# Power_Supply.net
KiCad netlist of a schematic drawn in Altium Designer
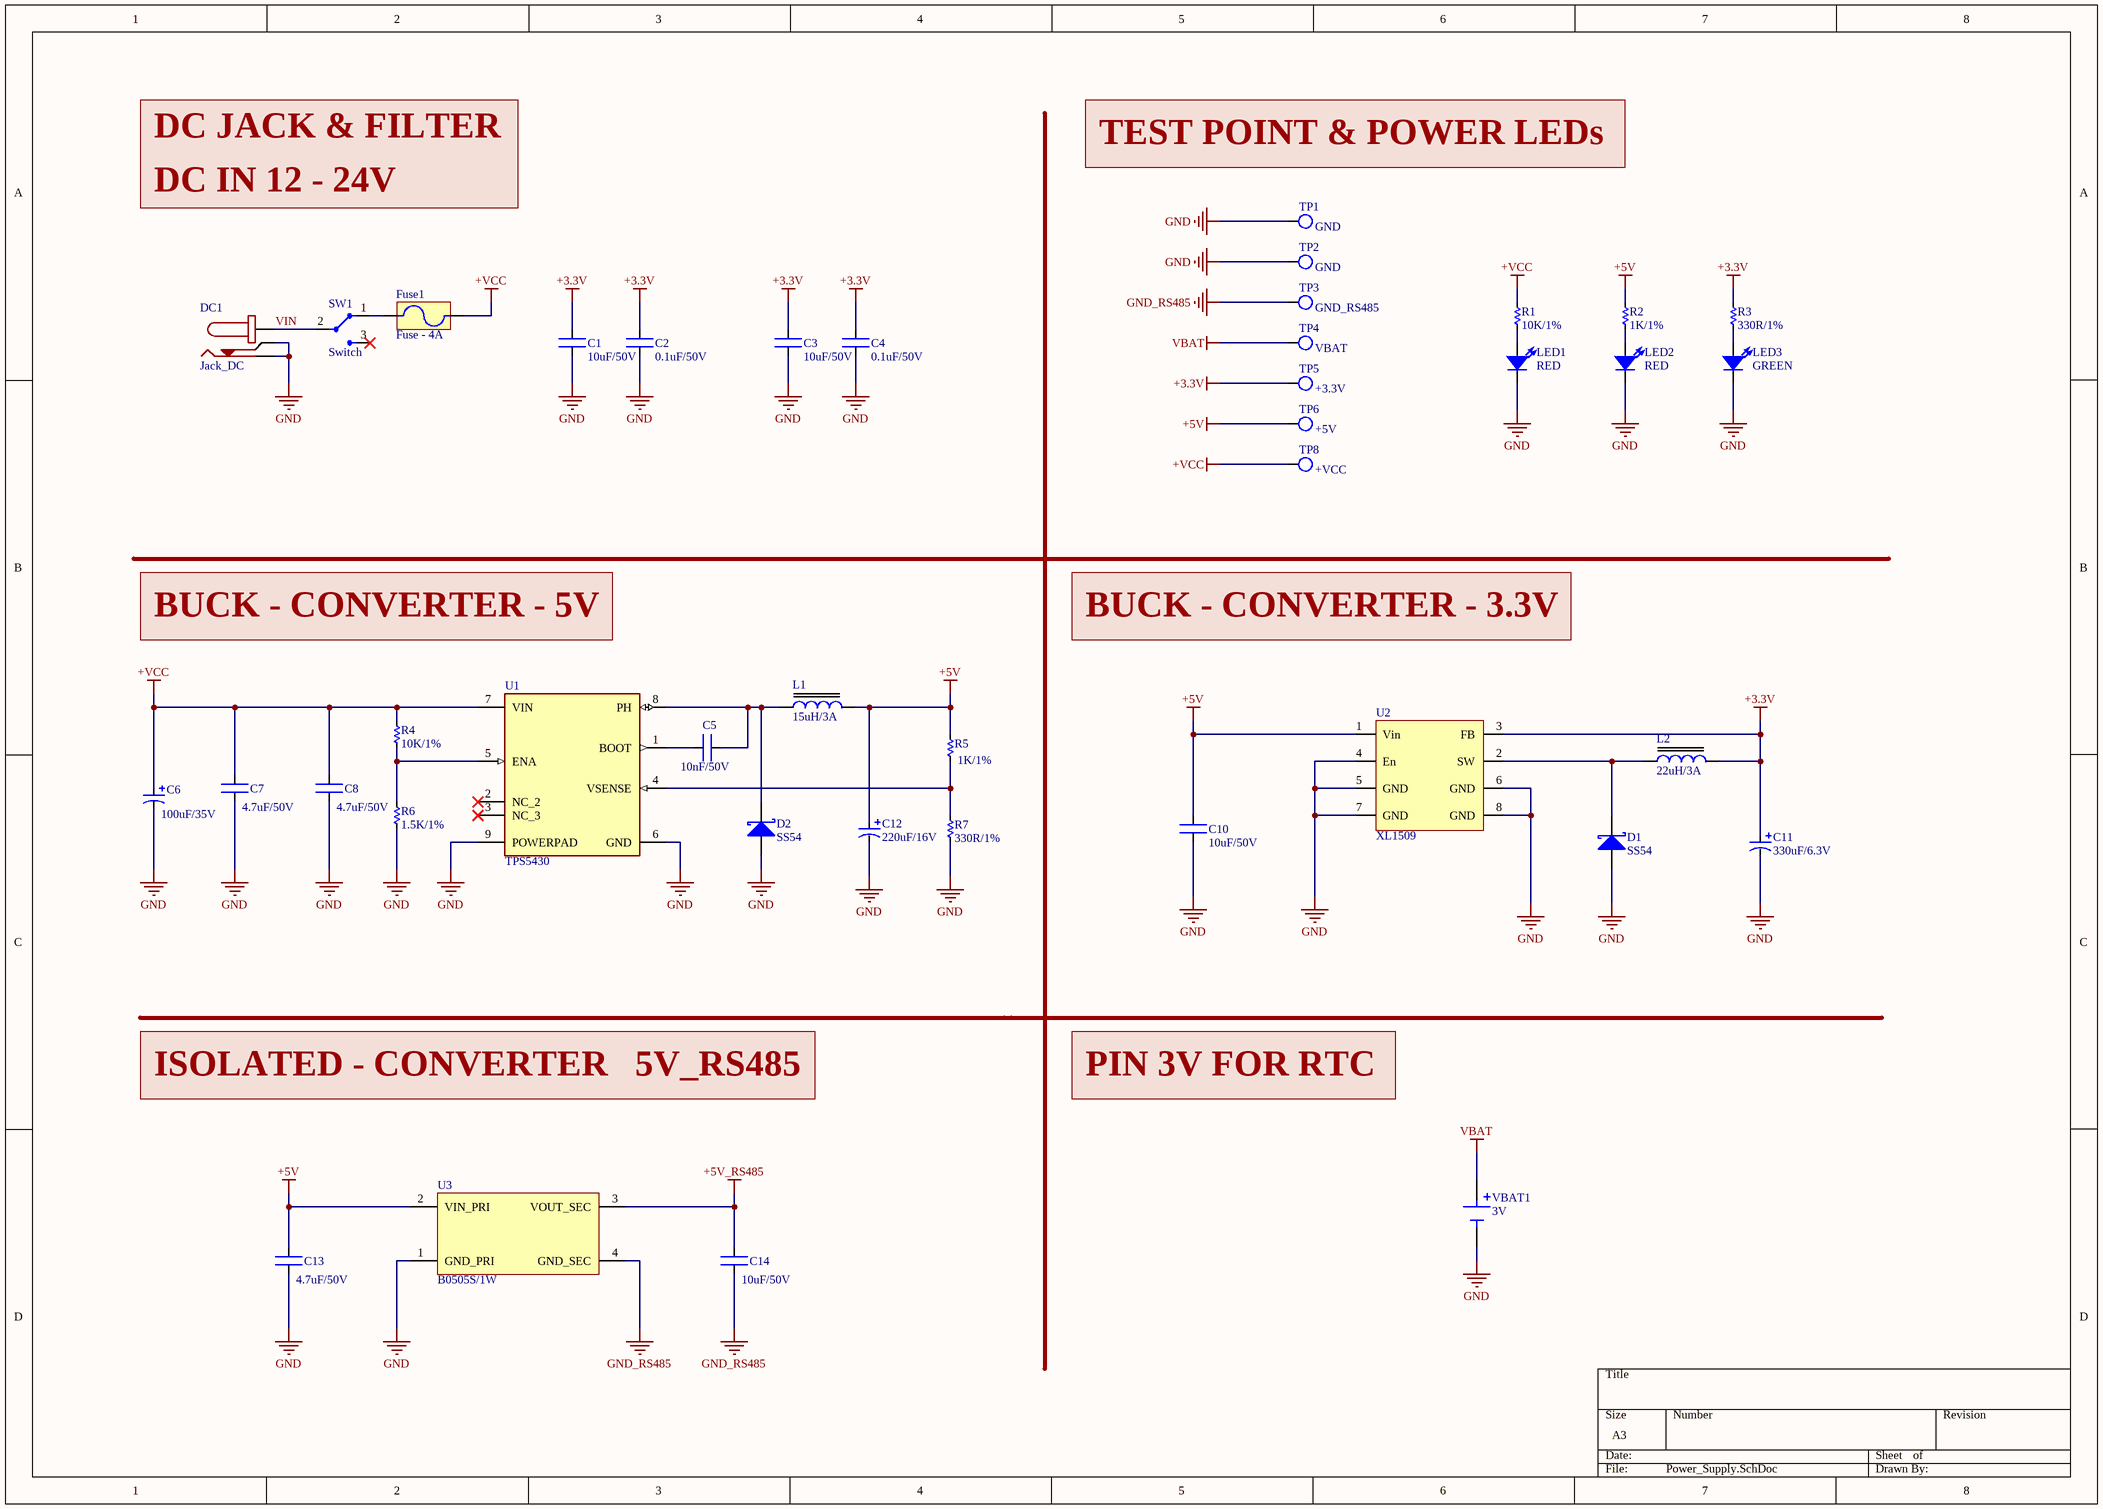
[diagram p0: Power_Supply.SchDoc]

(export (version "E")
  (design (tool "Eeschema 10.0.6"))
  (components
    (comp (ref "C1")
      (value "10uF/50V")
      (footprint "CAP - 0603")
      (description "CAPACITOR SMD - KEMET")
      (libsource (lib "NewLibrary") (part "CAPACITOR"))
    )
    (comp (ref "C2")
      (value "0.1uF/50V")
      (footprint "CAP - 0603")
      (description "CAPACITOR SMD - KEMET")
      (libsource (lib "NewLibrary") (part "CAPACITOR"))
    )
    (comp (ref "C3")
      (value "10uF/50V")
      (footprint "CAP - 0603")
      (description "CAPACITOR SMD - KEMET")
      (libsource (lib "NewLibrary") (part "CAPACITOR"))
    )
    (comp (ref "C4")
      (value "0.1uF/50V")
      (footprint "CAP - 0603")
      (description "CAPACITOR SMD - KEMET")
      (libsource (lib "NewLibrary") (part "CAPACITOR"))
    )
    (comp (ref "C5")
      (value "10nF/50V")
      (footprint "CAP - 0603")
      (description "CAPACITOR SMD - KEMET")
      (libsource (lib "NewLibrary") (part "CAPACITOR"))
    )
    (comp (ref "C6")
      (value "100uF/35V")
      (footprint "Alu_Cap_6.3_7.7")
      (libsource (lib "NewLibrary") (part "Alu_Capacitor"))
    )
    (comp (ref "C7")
      (value "4.7uF/50V")
      (footprint "CAP - 0603")
      (description "CAPACITOR SMD - KEMET")
      (libsource (lib "NewLibrary") (part "CAPACITOR"))
    )
    (comp (ref "C8")
      (value "4.7uF/50V")
      (footprint "CAP - 0603")
      (description "CAPACITOR SMD - KEMET")
      (libsource (lib "NewLibrary") (part "CAPACITOR"))
    )
    (comp (ref "C10")
      (value "10uF/50V")
      (footprint "CAP - 0603")
      (description "CAPACITOR SMD - KEMET")
      (libsource (lib "NewLibrary") (part "CAPACITOR"))
    )
    (comp (ref "C11")
      (value "330uF/6.3V")
      (footprint "Alu_Cap_6.3_7.7")
      (libsource (lib "NewLibrary") (part "Alu_Capacitor"))
    )
    (comp (ref "C12")
      (value "220uF/16V")
      (footprint "Alu_Cap_6.3_7.7")
      (libsource (lib "NewLibrary") (part "Alu_Capacitor"))
    )
    (comp (ref "C13")
      (value "4.7uF/50V")
      (footprint "CAP - 0603")
      (description "CAPACITOR SMD - KEMET")
      (libsource (lib "NewLibrary") (part "CAPACITOR"))
    )
    (comp (ref "C14")
      (value "10uF/50V")
      (footprint "CAP - 0603")
      (description "CAPACITOR SMD - KEMET")
      (libsource (lib "NewLibrary") (part "CAPACITOR"))
    )
    (comp (ref "D1")
      (value "SS54")
      (footprint "SS54")
      (description "DIODE SCHOTTKY 40V 5A SMA")
      (libsource (lib "NewLibrary") (part "SS54"))
    )
    (comp (ref "D2")
      (value "SS54")
      (footprint "SS54")
      (description "DIODE SCHOTTKY 40V 5A SMA")
      (libsource (lib "NewLibrary") (part "SS54"))
    )
    (comp (ref "DC1")
      (value "Jack_DC")
      (footprint "DC_5.5 x 2.1mm")
      (description "Jack DC IN (Hole)")
      (libsource (lib "NewLibrary") (part "Jack_DC"))
    )
    (comp (ref "Fuse1")
      (value "Fuse - 4A")
      (footprint "SMD-2")
      (description "Nano2 SMD FF submin fuse w/holder, 4A ¦ Littelfuse 0154004.DR")
      (libsource (lib "NewLibrary") (part "Fuse"))
    )
    (comp (ref "L1")
      (value "15uH/3A")
      (footprint "L_SMD_0630")
      (libsource (lib "NewLibrary") (part "Inductor_1_SMD"))
    )
    (comp (ref "L2")
      (value "22uH/3A")
      (footprint "L_SMD_0630")
      (libsource (lib "NewLibrary") (part "Inductor_1_SMD"))
    )
    (comp (ref "LED1")
      (value "RED")
      (footprint "RED_LED_0603")
      (description "LED SMD")
      (libsource (lib "NewLibrary") (part "LED_SMD"))
    )
    (comp (ref "LED2")
      (value "RED")
      (footprint "RED_LED_0603")
      (description "LED SMD")
      (libsource (lib "NewLibrary") (part "LED_SMD"))
    )
    (comp (ref "LED3")
      (value "GREEN")
      (footprint "GREEN_LED_0603")
      (description "LED SMD")
      (libsource (lib "NewLibrary") (part "LED_SMD"))
    )
    (comp (ref "R1")
      (value "10K/1%")
      (footprint "RES - 0603")
      (description "Resistor SMD - YAGEO")
      (libsource (lib "NewLibrary") (part "RESISTOR"))
    )
    (comp (ref "R2")
      (value "1K/1%")
      (footprint "RES - 0603")
      (description "Resistor SMD - YAGEO")
      (libsource (lib "NewLibrary") (part "RESISTOR"))
    )
    (comp (ref "R3")
      (value "330R/1%")
      (footprint "RES - 0603")
      (description "Resistor SMD - YAGEO")
      (libsource (lib "NewLibrary") (part "RESISTOR"))
    )
    (comp (ref "R4")
      (value "10K/1%")
      (footprint "RES - 0603")
      (description "Resistor SMD - YAGEO")
      (libsource (lib "NewLibrary") (part "RESISTOR"))
    )
    (comp (ref "R5")
      (value "1K/1%")
      (footprint "RES - 0603")
      (description "Resistor SMD - YAGEO")
      (libsource (lib "NewLibrary") (part "RESISTOR"))
    )
    (comp (ref "R6")
      (value "1.5K/1%")
      (footprint "RES - 0603")
      (description "Resistor SMD - YAGEO")
      (libsource (lib "NewLibrary") (part "RESISTOR"))
    )
    (comp (ref "R7")
      (value "330R/1%")
      (footprint "RES - 0603")
      (description "Resistor SMD - YAGEO")
      (libsource (lib "NewLibrary") (part "RESISTOR"))
    )
    (comp (ref "SW1")
      (value "Switch")
      (footprint "Dip_Switch_3_pins_0")
      (description "Switch 3 Pins")
      (libsource (lib "NewLibrary") (part "Switch"))
    )
    (comp (ref "TP1")
      (value "GND")
      (footprint "Test Point")
      (description "Test Point")
      (libsource (lib "NewLibrary") (part "TEST POINT"))
    )
    (comp (ref "TP2")
      (value "GND")
      (footprint "Test Point")
      (description "Test Point")
      (libsource (lib "NewLibrary") (part "TEST POINT"))
    )
    (comp (ref "TP3")
      (value "GND_RS485")
      (footprint "Test Point")
      (description "Test Point")
      (libsource (lib "NewLibrary") (part "TEST POINT"))
    )
    (comp (ref "TP4")
      (value "VBAT")
      (footprint "Test Point")
      (description "Test Point")
      (libsource (lib "NewLibrary") (part "TEST POINT"))
    )
    (comp (ref "TP5")
      (value "+3.3V")
      (footprint "Test Point")
      (description "Test Point")
      (libsource (lib "NewLibrary") (part "TEST POINT"))
    )
    (comp (ref "TP6")
      (value "+5V")
      (footprint "Test Point")
      (description "Test Point")
      (libsource (lib "NewLibrary") (part "TEST POINT"))
    )
    (comp (ref "TP8")
      (value "+VCC")
      (footprint "Test Point")
      (description "Test Point")
      (libsource (lib "NewLibrary") (part "TEST POINT"))
    )
    (comp (ref "U1")
      (value "TPS5430")
      (footprint "TPS5430")
      (description "Buck DC to DC Converter")
      (libsource (lib "NewLibrary") (part "TPS5430"))
    )
    (comp (ref "U2")
      (value "XL1509")
      (footprint "SOP_8")
      (description "Buck Converter")
      (libsource (lib "NewLibrary") (part "XL1509"))
    )
    (comp (ref "U3")
      (value "B0505S/1W")
      (footprint "B0505S/1W")
      (description "Isolated - Converter")
      (libsource (lib "NewLibrary") (part "B0505S/1W"))
    )
    (comp (ref "VBAT1")
      (value "3V")
      (footprint "CR2032 - SMD")
      (description "Battery Base CR2032")
      (libsource (lib "NewLibrary") (part "Battery Base"))
    )
  )
  (nets
    (net (code "1") (name "+3.3V") (class "Default")
      (node (ref "C1") (pin "1") (pinfunction "1_1") (pintype "passive"))
      (node (ref "C11") (pin "1") (pinfunction "1_1") (pintype "passive"))
      (node (ref "C2") (pin "1") (pinfunction "1_1") (pintype "passive"))
      (node (ref "C3") (pin "1") (pinfunction "1_1") (pintype "passive"))
      (node (ref "C4") (pin "1") (pinfunction "1_1") (pintype "passive"))
      (node (ref "L2") (pin "2") (pinfunction "5_2") (pintype "passive"))
      (node (ref "R3") (pin "1") (pinfunction "1_1") (pintype "passive"))
      (node (ref "TP5") (pin "1") (pinfunction "1_1") (pintype "passive"))
      (node (ref "U2") (pin "3") (pinfunction "FB_3") (pintype "passive"))
    )
    (net (code "2") (name "+5V") (class "Default")
      (node (ref "C10") (pin "1") (pinfunction "1_1") (pintype "passive"))
      (node (ref "C12") (pin "1") (pinfunction "1_1") (pintype "passive"))
      (node (ref "C13") (pin "1") (pinfunction "1_1") (pintype "passive"))
      (node (ref "L1") (pin "2") (pinfunction "5_2") (pintype "passive"))
      (node (ref "R2") (pin "1") (pinfunction "1_1") (pintype "passive"))
      (node (ref "R5") (pin "1") (pinfunction "1_1") (pintype "passive"))
      (node (ref "TP6") (pin "1") (pinfunction "1_1") (pintype "passive"))
      (node (ref "U2") (pin "1") (pinfunction "Vin_1") (pintype "passive"))
      (node (ref "U3") (pin "2") (pinfunction "VIN_PRI_2") (pintype "passive"))
    )
    (net (code "3") (name "+5V_RS485") (class "Default")
      (node (ref "C14") (pin "1") (pinfunction "1_1") (pintype "passive"))
      (node (ref "U3") (pin "3") (pinfunction "VOUT_SEC_3") (pintype "passive"))
    )
    (net (code "4") (name "+VCC") (class "Default")
      (node (ref "C6") (pin "1") (pinfunction "1_1") (pintype "passive"))
      (node (ref "C7") (pin "1") (pinfunction "1_1") (pintype "passive"))
      (node (ref "C8") (pin "1") (pinfunction "1_1") (pintype "passive"))
      (node (ref "Fuse1") (pin "2") (pinfunction "2_2") (pintype "passive"))
      (node (ref "R1") (pin "1") (pinfunction "1_1") (pintype "passive"))
      (node (ref "R4") (pin "1") (pinfunction "1_1") (pintype "passive"))
      (node (ref "TP8") (pin "1") (pinfunction "1_1") (pintype "passive"))
      (node (ref "U1") (pin "7") (pinfunction "VIN_7") (pintype "power_in"))
    )
    (net (code "5") (name "/VIN") (class "Default")
      (node (ref "DC1") (pin "1") (pinfunction "S_1") (pintype "power_in"))
      (node (ref "SW1") (pin "2") (pintype "passive"))
    )
    (net (code "6") (name "GND") (class "Default")
      (node (ref "C1") (pin "2") (pinfunction "2_2") (pintype "passive"))
      (node (ref "C10") (pin "2") (pinfunction "2_2") (pintype "passive"))
      (node (ref "C11") (pin "2") (pinfunction "2_2") (pintype "passive"))
      (node (ref "C12") (pin "2") (pinfunction "2_2") (pintype "passive"))
      (node (ref "C13") (pin "2") (pinfunction "2_2") (pintype "passive"))
      (node (ref "C2") (pin "2") (pinfunction "2_2") (pintype "passive"))
      (node (ref "C3") (pin "2") (pinfunction "2_2") (pintype "passive"))
      (node (ref "C4") (pin "2") (pinfunction "2_2") (pintype "passive"))
      (node (ref "C6") (pin "2") (pinfunction "2_2") (pintype "passive"))
      (node (ref "C7") (pin "2") (pinfunction "2_2") (pintype "passive"))
      (node (ref "C8") (pin "2") (pinfunction "2_2") (pintype "passive"))
      (node (ref "D1") (pin "1") (pinfunction "A_1") (pintype "passive"))
      (node (ref "D2") (pin "1") (pinfunction "A_1") (pintype "passive"))
      (node (ref "DC1") (pin "2") (pinfunction "TN_2") (pintype "passive"))
      (node (ref "DC1") (pin "3") (pinfunction "T_3") (pintype "passive"))
      (node (ref "LED1") (pin "2") (pinfunction "2_2") (pintype "passive"))
      (node (ref "LED2") (pin "2") (pinfunction "2_2") (pintype "passive"))
      (node (ref "LED3") (pin "2") (pinfunction "2_2") (pintype "passive"))
      (node (ref "R6") (pin "2") (pinfunction "2_2") (pintype "passive"))
      (node (ref "R7") (pin "2") (pinfunction "2_2") (pintype "passive"))
      (node (ref "TP1") (pin "1") (pinfunction "1_1") (pintype "passive"))
      (node (ref "TP2") (pin "1") (pinfunction "1_1") (pintype "passive"))
      (node (ref "U1") (pin "6") (pinfunction "GND_6") (pintype "passive"))
      (node (ref "U1") (pin "9") (pinfunction "POWERPAD_9") (pintype "passive"))
      (node (ref "U2") (pin "4") (pinfunction "En_4") (pintype "passive"))
      (node (ref "U2") (pin "5") (pinfunction "GND_5") (pintype "passive"))
      (node (ref "U2") (pin "6") (pinfunction "GND_6") (pintype "passive"))
      (node (ref "U2") (pin "7") (pinfunction "GND_7") (pintype "passive"))
      (node (ref "U2") (pin "8") (pinfunction "GND_8") (pintype "passive"))
      (node (ref "U3") (pin "1") (pinfunction "GND_PRI_1") (pintype "passive"))
      (node (ref "VBAT1") (pin "N") (pinfunction "NEG_N") (pintype "passive"))
    )
    (net (code "7") (name "GND_RS485") (class "Default")
      (node (ref "C14") (pin "2") (pinfunction "2_2") (pintype "passive"))
      (node (ref "TP3") (pin "1") (pinfunction "1_1") (pintype "passive"))
      (node (ref "U3") (pin "4") (pinfunction "GND_SEC_4") (pintype "passive"))
    )
    (net (code "8") (name "Net-(D1-K)") (class "Default")
      (node (ref "D1") (pin "2") (pinfunction "K_2") (pintype "passive"))
      (node (ref "L2") (pin "1") (pinfunction "4_1") (pintype "passive"))
      (node (ref "U2") (pin "2") (pinfunction "SW_2") (pintype "passive"))
    )
    (net (code "9") (name "Net-(D2-K)") (class "Default")
      (node (ref "C5") (pin "2") (pinfunction "2_2") (pintype "passive"))
      (node (ref "D2") (pin "2") (pinfunction "K_2") (pintype "passive"))
      (node (ref "L1") (pin "1") (pinfunction "4_1") (pintype "passive"))
      (node (ref "U1") (pin "8") (pinfunction "PH_8") (pintype "bidirectional"))
    )
    (net (code "10") (name "Net-(Fuse1-Pad1)") (class "Default")
      (node (ref "Fuse1") (pin "1") (pinfunction "1_1") (pintype "passive"))
      (node (ref "SW1") (pin "1") (pintype "passive"))
    )
    (net (code "11") (name "Net-(LED1-Pad1)") (class "Default")
      (node (ref "LED1") (pin "1") (pinfunction "1_1") (pintype "passive"))
      (node (ref "R1") (pin "2") (pinfunction "2_2") (pintype "passive"))
    )
    (net (code "12") (name "Net-(LED2-Pad1)") (class "Default")
      (node (ref "LED2") (pin "1") (pinfunction "1_1") (pintype "passive"))
      (node (ref "R2") (pin "2") (pinfunction "2_2") (pintype "passive"))
    )
    (net (code "13") (name "Net-(LED3-Pad1)") (class "Default")
      (node (ref "LED3") (pin "1") (pinfunction "1_1") (pintype "passive"))
      (node (ref "R3") (pin "2") (pinfunction "2_2") (pintype "passive"))
    )
    (net (code "14") (name "Net-(U1-BOOT)") (class "Default")
      (node (ref "C5") (pin "1") (pinfunction "1_1") (pintype "passive"))
      (node (ref "U1") (pin "1") (pinfunction "BOOT_1") (pintype "output"))
    )
    (net (code "15") (name "Net-(U1-ENA)") (class "Default")
      (node (ref "R4") (pin "2") (pinfunction "2_2") (pintype "passive"))
      (node (ref "R6") (pin "1") (pinfunction "1_1") (pintype "passive"))
      (node (ref "U1") (pin "5") (pinfunction "ENA_5") (pintype "input"))
    )
    (net (code "16") (name "Net-(U1-VSENSE)") (class "Default")
      (node (ref "R5") (pin "2") (pinfunction "2_2") (pintype "passive"))
      (node (ref "R7") (pin "1") (pinfunction "1_1") (pintype "passive"))
      (node (ref "U1") (pin "4") (pinfunction "VSENSE_4") (pintype "input"))
    )
    (net (code "17") (name "VBAT") (class "Default")
      (node (ref "TP4") (pin "1") (pinfunction "1_1") (pintype "passive"))
      (node (ref "VBAT1") (pin "P") (pinfunction "POS_P") (pintype "passive"))
    )
    (net (code "18") (name "unconnected-(SW1-I{slash}O2-Pad3)") (class "Default")
      (node (ref "SW1") (pin "3") (pinfunction "I/O2_3") (pintype "passive+no_connect"))
    )
    (net (code "19") (name "unconnected-(U1-NC_2-Pad2)") (class "Default")
      (node (ref "U1") (pin "2") (pinfunction "NC_2_2") (pintype "passive+no_connect"))
    )
    (net (code "20") (name "unconnected-(U1-NC_3-Pad3)") (class "Default")
      (node (ref "U1") (pin "3") (pinfunction "NC_3_3") (pintype "passive+no_connect"))
    )
  )
)
